# relaycircuit.net
KiCad netlist of a schematic drawn in EAGLE
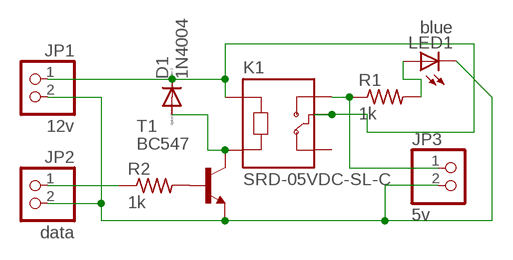
[diagram p0: schematic, sheet 1]

(export (version "E")
  (design (tool "Eeschema 10.0.6"))
  (components
    (comp (ref "D1")
      (value "1N4004")
      (footprint "eagle-import:DO41-10")
      (libsource (lib "eagle-import") (part "1N4004"))
    )
    (comp (ref "JP1")
      (value "12v")
      (footprint "eagle-import:1X02")
      (libsource (lib "eagle-import") (part "PINHD-1X2"))
    )
    (comp (ref "JP2")
      (value "data")
      (footprint "eagle-import:1X02")
      (libsource (lib "eagle-import") (part "PINHD-1X2"))
    )
    (comp (ref "JP3")
      (value "5v")
      (footprint "eagle-import:1X02")
      (libsource (lib "eagle-import") (part "PINHD-1X2"))
    )
    (comp (ref "K1")
      (value "SRD-05VDC-SL-C")
      (footprint "eagle-import:RELAY_SRD-05VDC-SL-C")
      (fields (field (name "MF") "Songle Relay"))
      (libsource (lib "eagle-import") (part "SRD-05VDC-SL-C"))
    )
    (comp (ref "LED1")
      (value "blue")
      (footprint "eagle-import:LED5MM")
      (libsource (lib "eagle-import") (part "LED5MM"))
    )
    (comp (ref "R1")
      (value "1k")
      (footprint "eagle-import:0207_10")
      (libsource (lib "eagle-import") (part "R-US_0207/10"))
    )
    (comp (ref "R2")
      (value "1k")
      (footprint "eagle-import:0207_10")
      (libsource (lib "eagle-import") (part "R-US_0207/10"))
    )
    (comp (ref "T1")
      (value "BC547")
      (footprint "eagle-import:TO92")
      (libsource (lib "eagle-import") (part "BC547"))
    )
  )
  (nets
    (net (code "1") (name "Net-(D1-PadC)") (class "Default")
      (node (ref "D1") (pin "C") (pinfunction "C_C") (pintype "passive"))
      (node (ref "JP1") (pin "1") (pinfunction "1_1") (pintype "passive"))
      (node (ref "K1") (pin "A1") (pinfunction "A1_A1") (pintype "passive"))
      (node (ref "K1") (pin "COM") (pinfunction "COM_COM") (pintype "passive"))
    )
    (net (code "2") (name "Net-(JP2-Pad1)") (class "Default")
      (node (ref "JP2") (pin "1") (pinfunction "1_1") (pintype "passive"))
      (node (ref "R2") (pin "1") (pinfunction "1_1") (pintype "passive"))
    )
    (net (code "3") (name "Net-(JP3-Pad1)") (class "Default")
      (node (ref "JP3") (pin "1") (pinfunction "1_1") (pintype "passive"))
      (node (ref "K1") (pin "NO") (pinfunction "NO_NO") (pintype "passive"))
      (node (ref "R1") (pin "1") (pinfunction "1_1") (pintype "passive"))
    )
    (net (code "4") (name "Net-(LED1-C)") (class "Default")
      (node (ref "JP1") (pin "2") (pinfunction "2_2") (pintype "passive"))
      (node (ref "JP2") (pin "2") (pinfunction "2_2") (pintype "passive"))
      (node (ref "JP3") (pin "2") (pinfunction "2_2") (pintype "passive"))
      (node (ref "LED1") (pin "K") (pinfunction "C_K") (pintype "passive"))
      (node (ref "T1") (pin "1") (pinfunction "E_1") (pintype "passive"))
    )
    (net (code "5") (name "Net-(LED1-PadA)") (class "Default")
      (node (ref "LED1") (pin "A") (pinfunction "A_A") (pintype "passive"))
      (node (ref "R1") (pin "2") (pinfunction "2_2") (pintype "passive"))
    )
    (net (code "6") (name "Net-(T1-B)") (class "Default")
      (node (ref "R2") (pin "2") (pinfunction "2_2") (pintype "passive"))
      (node (ref "T1") (pin "2") (pinfunction "B_2") (pintype "passive"))
    )
    (net (code "7") (name "Net-(T1-C)") (class "Default")
      (node (ref "D1") (pin "A") (pinfunction "A_A") (pintype "passive"))
      (node (ref "K1") (pin "A2") (pinfunction "A2_A2") (pintype "passive"))
      (node (ref "T1") (pin "3") (pinfunction "C_3") (pintype "passive"))
    )
    (net (code "8") (name "unconnected-(K1-PadNC)") (class "Default")
      (node (ref "K1") (pin "NC") (pinfunction "NC_NC") (pintype "passive"))
    )
  )
)
